# Arduino__Connectors.net
KiCad netlist of a schematic drawn in Altium Designer
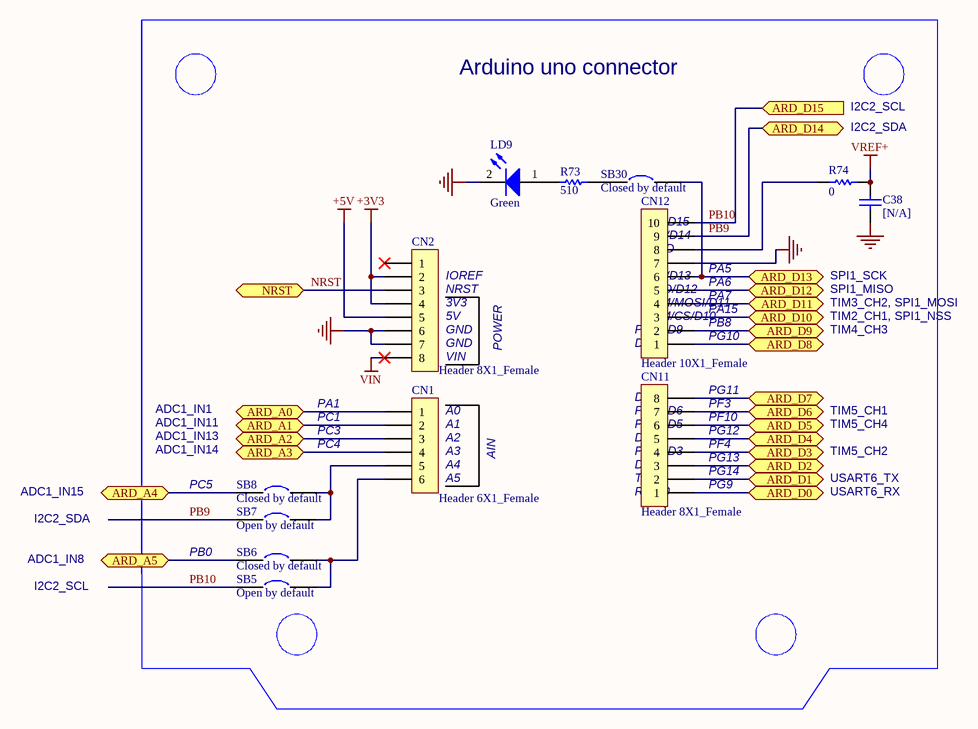
[diagram p0: Arduino_ Connectors.SchDoc]

(export (version "E")
  (design (tool "Eeschema 10.0.6"))
  (components
    (comp (ref "C38")
      (value "[N/A]")
      (footprint "0603C")
      (description "Capacitor")
      (fields (field (name "PUBLISHER") "Altium Limited"))
      (libsource (lib "Miscellaneous Devices") (part "Cap"))
    )
    (comp (ref "CN1")
      (value "Header 6X1_Female")
      (footprint "HDR_1X6_2R54_W")
      (description "Header, 6-Pin, Single row,female")
      (fields (field (name "PUBLISHER") "Altium Limited"))
      (libsource (lib "Nucleo_64") (part "Header 6X1_Female"))
    )
    (comp (ref "CN2")
      (value "Header 8X1_Female")
      (footprint "HDR_1X8_2R54_W")
      (description "Header, 8-Pin, Single row,female")
      (fields (field (name "PUBLISHER") "Altium Limited"))
      (libsource (lib "") (part "Header 8X1_Female_1"))
    )
    (comp (ref "CN11")
      (value "Header 8X1_Female")
      (footprint "HDR_1X8_2R54_W")
      (description "Header, 8-Pin, Single row,female")
      (fields (field (name "PUBLISHER") "Altium Limited"))
      (libsource (lib "Nucleo_64") (part "Header 8X1_Female"))
    )
    (comp (ref "CN12")
      (value "Header 10X1_Female")
      (footprint "HDR_1X10_2R54_W")
      (description "Header, 10-Pin, Single row,female")
      (fields (field (name "PUBLISHER") "Altium Limited"))
      (libsource (lib "Nucleo_64") (part "Header 10X1_Female"))
    )
    (comp (ref "LD9")
      (value "Green")
      (footprint "0603D")
      (description "Typical RED, GREEN, YELLOW, AMBER GaAs LED")
      (fields (field (name "PUBLISHER") "Altium Limited"))
      (libsource (lib "Miscellaneous Devices") (part "LED2"))
    )
    (comp (ref "R73")
      (value "510")
      (footprint "0603R")
      (description "Resistor")
      (fields (field (name "PUBLISHER") "Altium Limited"))
      (libsource (lib "Miscellaneous Devices") (part "Res1"))
    )
    (comp (ref "R74")
      (value "0")
      (footprint "SB_0603")
      (description "Resistor")
      (fields (field (name "PUBLISHER") "Altium Limited"))
      (libsource (lib "Miscellaneous Devices") (part "Res1"))
    )
    (comp (ref "SB5")
      (value "Open by default")
      (footprint "SB_0603")
      (description "Circuit Breaker")
      (fields (field (name "PUBLISHER") "Altium Limited"))
      (libsource (lib "Miscellaneous Devices") (part "Circuit Breaker"))
    )
    (comp (ref "SB6")
      (value "Closed by default")
      (footprint "SB_0603")
      (description "Circuit Breaker")
      (fields (field (name "PUBLISHER") "Altium Limited"))
      (libsource (lib "Miscellaneous Devices") (part "Circuit Breaker"))
    )
    (comp (ref "SB7")
      (value "Open by default")
      (footprint "SB_0603")
      (description "Circuit Breaker")
      (fields (field (name "PUBLISHER") "Altium Limited"))
      (libsource (lib "Miscellaneous Devices") (part "Circuit Breaker"))
    )
    (comp (ref "SB8")
      (value "Closed by default")
      (footprint "SB_0603")
      (description "Circuit Breaker")
      (fields (field (name "PUBLISHER") "Altium Limited"))
      (libsource (lib "Miscellaneous Devices") (part "Circuit Breaker"))
    )
    (comp (ref "SB30")
      (value "Closed by default")
      (footprint "SB_0603")
      (description "Circuit Breaker")
      (fields (field (name "PUBLISHER") "Altium Limited"))
      (libsource (lib "Miscellaneous Devices") (part "Circuit Breaker"))
    )
  )
  (nets
    (net (code "1") (name "+3V3") (class "Default")
      (node (ref "CN2") (pin "2") (pinfunction "2_2") (pintype "passive"))
      (node (ref "CN2") (pin "4") (pinfunction "4_4") (pintype "passive"))
    )
    (net (code "2") (name "+5V") (class "Default")
      (node (ref "CN2") (pin "5") (pinfunction "5_5") (pintype "passive"))
    )
    (net (code "3") (name "/ARD_A0") (class "Default")
      (node (ref "CN1") (pin "1") (pinfunction "1_1") (pintype "passive"))
    )
    (net (code "4") (name "/ARD_A1") (class "Default")
      (node (ref "CN1") (pin "2") (pinfunction "2_2") (pintype "passive"))
    )
    (net (code "5") (name "/ARD_A2") (class "Default")
      (node (ref "CN1") (pin "3") (pinfunction "3_3") (pintype "passive"))
    )
    (net (code "6") (name "/ARD_A3") (class "Default")
      (node (ref "CN1") (pin "4") (pinfunction "4_4") (pintype "passive"))
    )
    (net (code "7") (name "/ARD_A4") (class "Default")
      (node (ref "SB8") (pin "1") (pinfunction "1_1") (pintype "passive"))
    )
    (net (code "8") (name "/ARD_A5") (class "Default")
      (node (ref "SB6") (pin "1") (pinfunction "1_1") (pintype "passive"))
    )
    (net (code "9") (name "/ARD_D0") (class "Default")
      (node (ref "CN11") (pin "1") (pinfunction "1_1") (pintype "passive"))
    )
    (net (code "10") (name "/ARD_D1") (class "Default")
      (node (ref "CN11") (pin "2") (pinfunction "2_2") (pintype "passive"))
    )
    (net (code "11") (name "/ARD_D2") (class "Default")
      (node (ref "CN11") (pin "3") (pinfunction "3_3") (pintype "passive"))
    )
    (net (code "12") (name "/ARD_D3") (class "Default")
      (node (ref "CN11") (pin "4") (pinfunction "4_4") (pintype "passive"))
    )
    (net (code "13") (name "/ARD_D4") (class "Default")
      (node (ref "CN11") (pin "5") (pinfunction "5_5") (pintype "passive"))
    )
    (net (code "14") (name "/ARD_D5") (class "Default")
      (node (ref "CN11") (pin "6") (pinfunction "6_6") (pintype "passive"))
    )
    (net (code "15") (name "/ARD_D6") (class "Default")
      (node (ref "CN11") (pin "7") (pinfunction "7_7") (pintype "passive"))
    )
    (net (code "16") (name "/ARD_D7") (class "Default")
      (node (ref "CN11") (pin "8") (pinfunction "8_8") (pintype "passive"))
    )
    (net (code "17") (name "/ARD_D8") (class "Default")
      (node (ref "CN12") (pin "1") (pinfunction "1_1") (pintype "passive"))
    )
    (net (code "18") (name "/ARD_D9") (class "Default")
      (node (ref "CN12") (pin "2") (pinfunction "2_2") (pintype "passive"))
    )
    (net (code "19") (name "/ARD_D10") (class "Default")
      (node (ref "CN12") (pin "3") (pinfunction "3_3") (pintype "passive"))
    )
    (net (code "20") (name "/ARD_D11") (class "Default")
      (node (ref "CN12") (pin "4") (pinfunction "4_4") (pintype "passive"))
    )
    (net (code "21") (name "/ARD_D12") (class "Default")
      (node (ref "CN12") (pin "5") (pinfunction "5_5") (pintype "passive"))
    )
    (net (code "22") (name "/ARD_D13") (class "Default")
      (node (ref "CN12") (pin "6") (pinfunction "6_6") (pintype "passive"))
      (node (ref "SB30") (pin "2") (pinfunction "2_2") (pintype "passive"))
    )
    (net (code "23") (name "/NRST") (class "Default")
      (node (ref "CN2") (pin "3") (pinfunction "3_3") (pintype "passive"))
    )
    (net (code "24") (name "/PB9") (class "Default")
      (node (ref "CN12") (pin "9") (pinfunction "9_9") (pintype "passive"))
      (node (ref "SB7") (pin "1") (pinfunction "1_1") (pintype "passive"))
    )
    (net (code "25") (name "/PB10") (class "Default")
      (node (ref "CN12") (pin "10") (pinfunction "10_10") (pintype "passive"))
      (node (ref "SB5") (pin "1") (pinfunction "1_1") (pintype "passive"))
    )
    (net (code "26") (name "GND") (class "Default")
      (node (ref "C38") (pin "1") (pinfunction "1_1") (pintype "passive"))
      (node (ref "CN12") (pin "7") (pinfunction "7_7") (pintype "passive"))
      (node (ref "CN2") (pin "6") (pinfunction "6_6") (pintype "passive"))
      (node (ref "CN2") (pin "7") (pinfunction "7_7") (pintype "passive"))
      (node (ref "LD9") (pin "2") (pinfunction "K_2") (pintype "passive"))
    )
    (net (code "27") (name "Net-(CN1-Pad5)") (class "Default")
      (node (ref "CN1") (pin "5") (pinfunction "5_5") (pintype "passive"))
      (node (ref "SB7") (pin "2") (pinfunction "2_2") (pintype "passive"))
      (node (ref "SB8") (pin "2") (pinfunction "2_2") (pintype "passive"))
    )
    (net (code "28") (name "Net-(CN1-Pad6)") (class "Default")
      (node (ref "CN1") (pin "6") (pinfunction "6_6") (pintype "passive"))
      (node (ref "SB5") (pin "2") (pinfunction "2_2") (pintype "passive"))
      (node (ref "SB6") (pin "2") (pinfunction "2_2") (pintype "passive"))
    )
    (net (code "29") (name "Net-(CN12-Pad8)") (class "Default")
      (node (ref "CN12") (pin "8") (pinfunction "8_8") (pintype "passive"))
      (node (ref "R74") (pin "2") (pinfunction "2_2") (pintype "passive"))
    )
    (net (code "30") (name "Net-(LD9-A)") (class "Default")
      (node (ref "LD9") (pin "1") (pinfunction "A_1") (pintype "passive"))
      (node (ref "R73") (pin "2") (pinfunction "2_2") (pintype "passive"))
    )
    (net (code "31") (name "Net-(R73-Pad1)") (class "Default")
      (node (ref "R73") (pin "1") (pinfunction "1_1") (pintype "passive"))
      (node (ref "SB30") (pin "1") (pinfunction "1_1") (pintype "passive"))
    )
    (net (code "32") (name "VIN") (class "Default")
      (node (ref "CN2") (pin "8") (pinfunction "8_8") (pintype "passive"))
    )
    (net (code "33") (name "VREF+") (class "Default")
      (node (ref "C38") (pin "2") (pinfunction "2_2") (pintype "passive"))
      (node (ref "R74") (pin "1") (pinfunction "1_1") (pintype "passive"))
    )
    (net (code "34") (name "unconnected-(CN2-Pad1)") (class "Default")
      (node (ref "CN2") (pin "1") (pinfunction "1_1") (pintype "passive+no_connect"))
    )
  )
)
